# F_BRIGE.net
KiCad netlist of a schematic drawn in EAGLE
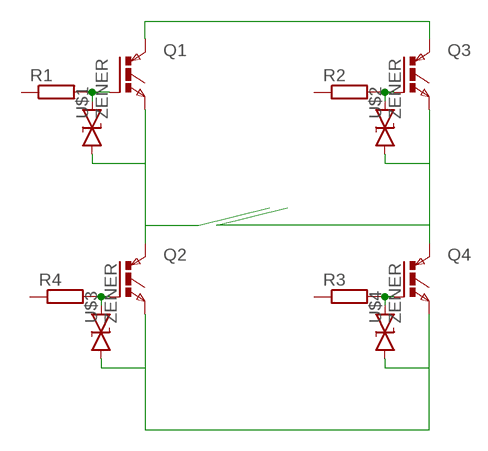
[diagram p0: schematic, sheet 1]

(export (version "E")
  (design (tool "Eeschema 10.0.6"))
  (components
    (comp (ref "Q1")
      (value "IGBTTO247H")
      (footprint "eagle-import:TO247BH")
      (libsource (lib "eagle-import") (part "IGBTTO247H"))
    )
    (comp (ref "Q2")
      (value "IGBTTO247H")
      (footprint "eagle-import:TO247BH")
      (libsource (lib "eagle-import") (part "IGBTTO247H"))
    )
    (comp (ref "Q3")
      (value "IGBTTO247H")
      (footprint "eagle-import:TO247BH")
      (libsource (lib "eagle-import") (part "IGBTTO247H"))
    )
    (comp (ref "Q4")
      (value "IGBTTO247H")
      (footprint "eagle-import:TO247BH")
      (libsource (lib "eagle-import") (part "IGBTTO247H"))
    )
    (comp (ref "R1")
      (value "R-EU_0414/5V")
      (footprint "eagle-import:0414V")
      (libsource (lib "eagle-import") (part "R-EU_0414/5V"))
    )
    (comp (ref "R2")
      (value "R-EU_0414/5V")
      (footprint "eagle-import:0414V")
      (libsource (lib "eagle-import") (part "R-EU_0414/5V"))
    )
    (comp (ref "R3")
      (value "R-EU_0414/5V")
      (footprint "eagle-import:0414V")
      (libsource (lib "eagle-import") (part "R-EU_0414/5V"))
    )
    (comp (ref "R4")
      (value "R-EU_0414/5V")
      (footprint "eagle-import:0414V")
      (libsource (lib "eagle-import") (part "R-EU_0414/5V"))
    )
    (comp (ref "U$1")
      (value "ZENER")
      (footprint "eagle-import:SMA-DIODE")
      (libsource (lib "eagle-import") (part "ZENER"))
    )
    (comp (ref "U$2")
      (value "ZENER")
      (footprint "eagle-import:SMA-DIODE")
      (libsource (lib "eagle-import") (part "ZENER"))
    )
    (comp (ref "U$3")
      (value "ZENER")
      (footprint "eagle-import:SMA-DIODE")
      (libsource (lib "eagle-import") (part "ZENER"))
    )
    (comp (ref "U$4")
      (value "ZENER")
      (footprint "eagle-import:SMA-DIODE")
      (libsource (lib "eagle-import") (part "ZENER"))
    )
  )
  (nets
    (net (code "1") (name "Net-(Q1-C)") (class "Default")
      (node (ref "Q1") (pin "D") (pinfunction "C_D") (pintype "passive"))
      (node (ref "Q3") (pin "D") (pinfunction "C_D") (pintype "passive"))
    )
    (net (code "2") (name "Net-(Q1-E)") (class "Default")
      (node (ref "Q1") (pin "S") (pinfunction "E_S") (pintype "passive"))
      (node (ref "Q2") (pin "D") (pinfunction "C_D") (pintype "passive"))
      (node (ref "U$1") (pin "A") (pinfunction "A_A") (pintype "passive"))
    )
    (net (code "3") (name "Net-(Q1-PadG)") (class "Default")
      (node (ref "Q1") (pin "G") (pinfunction "G_G") (pintype "passive"))
      (node (ref "R1") (pin "2") (pinfunction "2_2") (pintype "passive"))
      (node (ref "U$1") (pin "C") (pinfunction "C_C") (pintype "passive"))
    )
    (net (code "4") (name "Net-(Q2-E)") (class "Default")
      (node (ref "Q2") (pin "S") (pinfunction "E_S") (pintype "passive"))
      (node (ref "Q4") (pin "S") (pinfunction "E_S") (pintype "passive"))
      (node (ref "U$3") (pin "A") (pinfunction "A_A") (pintype "passive"))
      (node (ref "U$4") (pin "A") (pinfunction "A_A") (pintype "passive"))
    )
    (net (code "5") (name "Net-(Q2-PadG)") (class "Default")
      (node (ref "Q2") (pin "G") (pinfunction "G_G") (pintype "passive"))
      (node (ref "R4") (pin "2") (pinfunction "2_2") (pintype "passive"))
      (node (ref "U$3") (pin "C") (pinfunction "C_C") (pintype "passive"))
    )
    (net (code "6") (name "Net-(Q3-E)") (class "Default")
      (node (ref "Q3") (pin "S") (pinfunction "E_S") (pintype "passive"))
      (node (ref "Q4") (pin "D") (pinfunction "C_D") (pintype "passive"))
      (node (ref "U$2") (pin "A") (pinfunction "A_A") (pintype "passive"))
    )
    (net (code "7") (name "Net-(Q3-PadG)") (class "Default")
      (node (ref "Q3") (pin "G") (pinfunction "G_G") (pintype "passive"))
      (node (ref "R2") (pin "2") (pinfunction "2_2") (pintype "passive"))
      (node (ref "U$2") (pin "C") (pinfunction "C_C") (pintype "passive"))
    )
    (net (code "8") (name "Net-(Q4-PadG)") (class "Default")
      (node (ref "Q4") (pin "G") (pinfunction "G_G") (pintype "passive"))
      (node (ref "R3") (pin "2") (pinfunction "2_2") (pintype "passive"))
      (node (ref "U$4") (pin "C") (pinfunction "C_C") (pintype "passive"))
    )
    (net (code "9") (name "unconnected-(R1-Pad1)") (class "Default")
      (node (ref "R1") (pin "1") (pinfunction "1_1") (pintype "passive"))
    )
    (net (code "10") (name "unconnected-(R2-Pad1)") (class "Default")
      (node (ref "R2") (pin "1") (pinfunction "1_1") (pintype "passive"))
    )
    (net (code "11") (name "unconnected-(R3-Pad1)") (class "Default")
      (node (ref "R3") (pin "1") (pinfunction "1_1") (pintype "passive"))
    )
    (net (code "12") (name "unconnected-(R4-Pad1)") (class "Default")
      (node (ref "R4") (pin "1") (pinfunction "1_1") (pintype "passive"))
    )
  )
)
